# RocMan.net
KiCad netlist of a schematic drawn in EAGLE
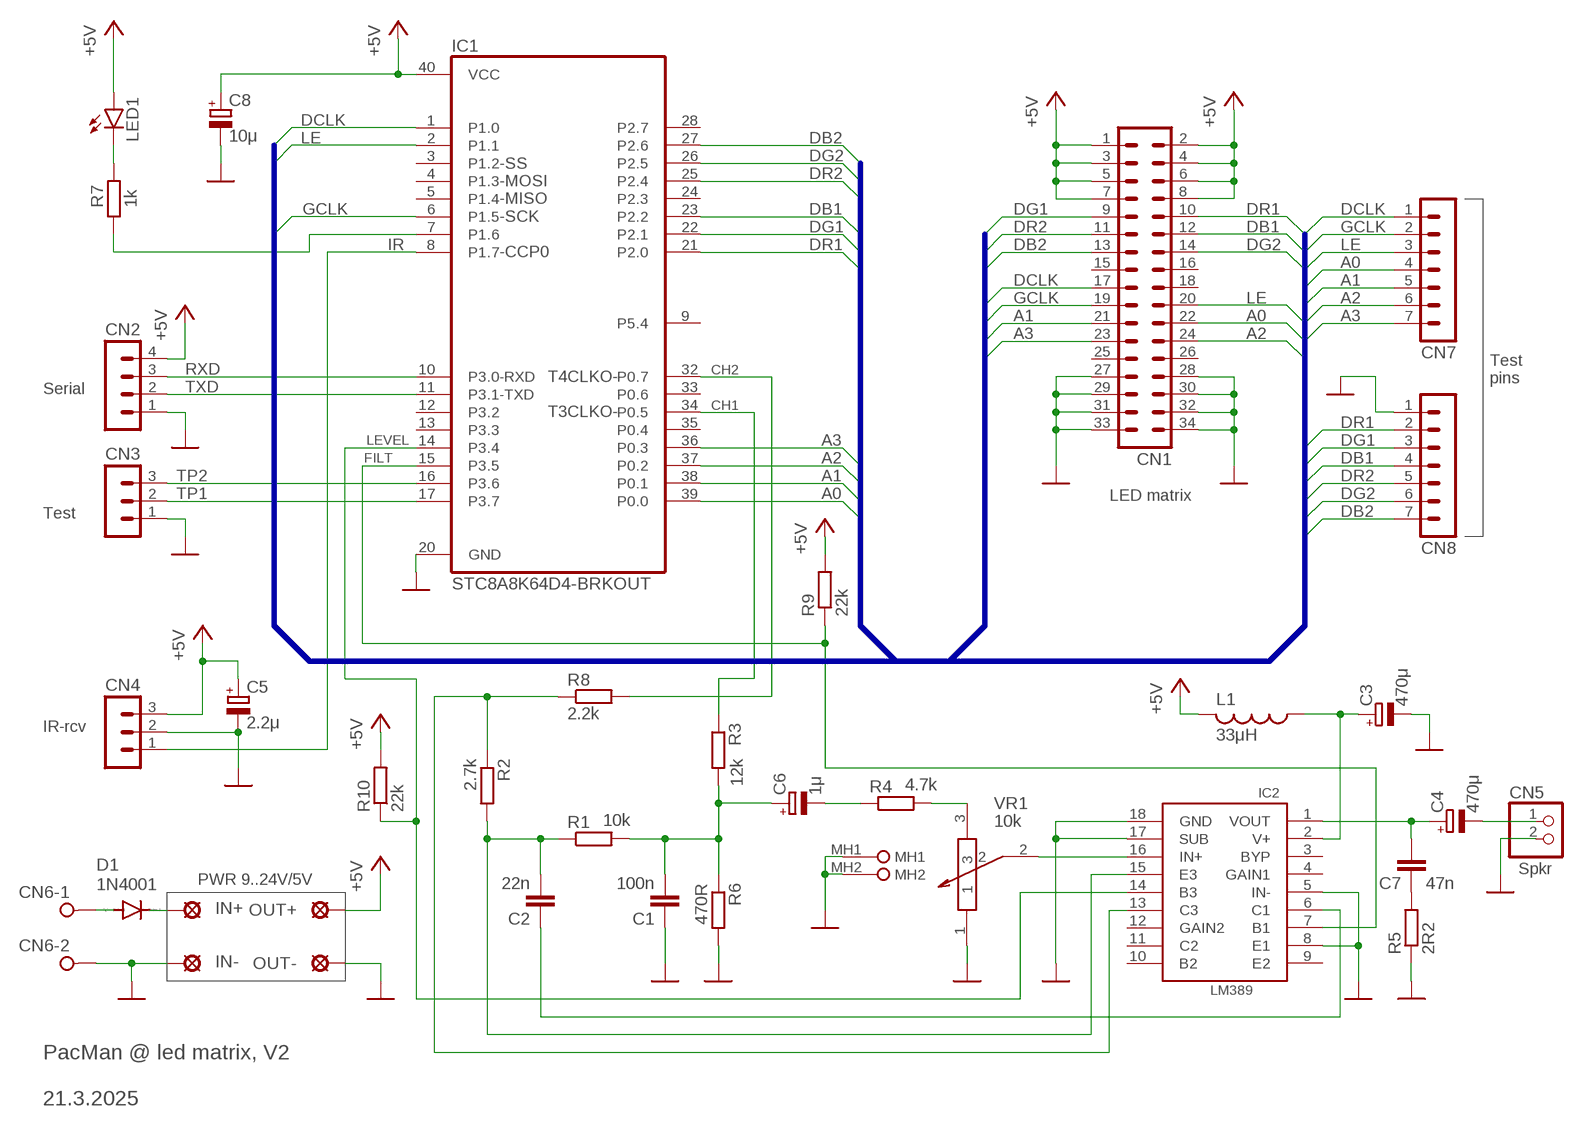
[diagram p0: schematic, sheet 1]

(export (version "E")
  (design (tool "Eeschema 10.0.6"))
  (components
    (comp (ref "C1")
      (value "100n")
      (footprint "eagle-import:C0805")
      (libsource (lib "eagle-import") (part "C-EUC0805"))
    )
    (comp (ref "C2")
      (value "22n")
      (footprint "eagle-import:C0805")
      (libsource (lib "eagle-import") (part "C-EUC0805"))
    )
    (comp (ref "C3")
      (value "470μ")
      (footprint "eagle-import:E5-10,5")
      (libsource (lib "eagle-import") (part "CPOL-EUE5-10.5"))
    )
    (comp (ref "C4")
      (value "470μ")
      (footprint "eagle-import:E5-10,5")
      (libsource (lib "eagle-import") (part "CPOL-EUE5-10.5"))
    )
    (comp (ref "C5")
      (value "2.2μ")
      (footprint "eagle-import:SMC_A")
      (libsource (lib "eagle-import") (part "CPOL-EUSMCA"))
    )
    (comp (ref "C6")
      (value "1μ")
      (footprint "eagle-import:SMC_A")
      (libsource (lib "eagle-import") (part "CPOL-EUSMCA"))
    )
    (comp (ref "C7")
      (value "47n")
      (footprint "eagle-import:C0805")
      (libsource (lib "eagle-import") (part "C-EUC0805"))
    )
    (comp (ref "C8")
      (value "10μ")
      (footprint "eagle-import:SMC_A")
      (libsource (lib "eagle-import") (part "CPOL-EUSMCA"))
    )
    (comp (ref "CN1")
      (value "ML34")
      (footprint "eagle-import:ML34")
      (libsource (lib "eagle-import") (part "ML34"))
    )
    (comp (ref "CN2")
      (value "MA04-1")
      (footprint "eagle-import:MA04-1")
      (libsource (lib "eagle-import") (part "MA04-1"))
    )
    (comp (ref "CN3")
      (value "MA03-1")
      (footprint "eagle-import:MA03-1")
      (libsource (lib "eagle-import") (part "MA03-1"))
    )
    (comp (ref "CN4")
      (value "MA03-1")
      (footprint "eagle-import:MA03-1")
      (libsource (lib "eagle-import") (part "MA03-1"))
    )
    (comp (ref "CN5")
      (value "PINHD-1X2")
      (footprint "eagle-import:1X02")
      (libsource (lib "eagle-import") (part "PINHD-1X2"))
    )
    (comp (ref "CN6")
      (value "W237-02P")
      (footprint "eagle-import:W237-132")
      (libsource (lib "eagle-import") (part "W237-02P"))
    )
    (comp (ref "CN7")
      (value "MA07-1")
      (footprint "eagle-import:MA07-1")
      (libsource (lib "eagle-import") (part "MA07-1"))
    )
    (comp (ref "CN8")
      (value "MA07-1")
      (footprint "eagle-import:MA07-1")
      (libsource (lib "eagle-import") (part "MA07-1"))
    )
    (comp (ref "D1")
      (value "1N4001")
      (footprint "eagle-import:DO41-10")
      (libsource (lib "eagle-import") (part "1N4004"))
    )
    (comp (ref "IC1")
      (value "STC8A8K64D4-BRKOUT")
      (footprint "eagle-import:DIL40")
      (libsource (lib "eagle-import") (part "STC8A8K64D4-BRKOUT"))
    )
    (comp (ref "IC2")
      (value "LM389")
      (footprint "eagle-import:DIL18")
      (libsource (lib "eagle-import") (part "LM389"))
    )
    (comp (ref "IN+")
      (value "LSP11")
      (footprint "eagle-import:LSP11")
      (libsource (lib "eagle-import") (part "LSP11"))
    )
    (comp (ref "IN-")
      (value "LSP11")
      (footprint "eagle-import:LSP11")
      (libsource (lib "eagle-import") (part "LSP11"))
    )
    (comp (ref "L1")
      (value "33μH")
      (footprint "eagle-import:L4532M")
      (libsource (lib "eagle-import") (part "L-USL4532C"))
    )
    (comp (ref "LED1")
      (value "LEDCHIP-LED0805")
      (footprint "eagle-import:CHIP-LED0805")
      (libsource (lib "eagle-import") (part "LEDCHIP-LED0805"))
    )
    (comp (ref "OUT+")
      (value "LSP11")
      (footprint "eagle-import:LSP11")
      (libsource (lib "eagle-import") (part "LSP11"))
    )
    (comp (ref "OUT-")
      (value "LSP11")
      (footprint "eagle-import:LSP11")
      (libsource (lib "eagle-import") (part "LSP11"))
    )
    (comp (ref "R1")
      (value "10k")
      (footprint "eagle-import:R0805")
      (libsource (lib "eagle-import") (part "R-EU_R0805"))
    )
    (comp (ref "R2")
      (value "2.7k")
      (footprint "eagle-import:R0805")
      (libsource (lib "eagle-import") (part "R-EU_R0805"))
    )
    (comp (ref "R3")
      (value "12k")
      (footprint "eagle-import:R0805")
      (libsource (lib "eagle-import") (part "R-EU_R0805"))
    )
    (comp (ref "R4")
      (value "4.7k")
      (footprint "eagle-import:R0805")
      (libsource (lib "eagle-import") (part "R-EU_R0805"))
    )
    (comp (ref "R5")
      (value "2R2")
      (footprint "eagle-import:R0805")
      (libsource (lib "eagle-import") (part "R-EU_R0805"))
    )
    (comp (ref "R6")
      (value "470R")
      (footprint "eagle-import:R0805")
      (libsource (lib "eagle-import") (part "R-EU_R0805"))
    )
    (comp (ref "R7")
      (value "1k")
      (footprint "eagle-import:R0805")
      (libsource (lib "eagle-import") (part "R-EU_R0805"))
    )
    (comp (ref "R8")
      (value "2.2k")
      (footprint "eagle-import:R0805")
      (libsource (lib "eagle-import") (part "R-EU_R0805"))
    )
    (comp (ref "R9")
      (value "22k")
      (footprint "eagle-import:R0805")
      (libsource (lib "eagle-import") (part "R-EU_R0805"))
    )
    (comp (ref "R10")
      (value "22k")
      (footprint "eagle-import:R0805")
      (libsource (lib "eagle-import") (part "R-EU_R0805"))
    )
    (comp (ref "VR1")
      (value "10k")
      (footprint "eagle-import:PTV09A4015FA103")
      (fields
        (field (name "MANUFACTURER_PART_NUMBER") "PTV09A-4015F-A103")
        (field (name "MOUSER_PART_NUMBER") "652-PTV09A-4015FA103")
      )
      (libsource (lib "eagle-import") (part "PTV09A-4015F-A103"))
    )
  )
  (nets
    (net (code "1") (name "+5V") (class "Default")
      (node (ref "C5") (pin "+") (pinfunction "+_+") (pintype "passive"))
      (node (ref "C8") (pin "+") (pinfunction "+_+") (pintype "passive"))
      (node (ref "CN1") (pin "1") (pinfunction "1_1") (pintype "passive"))
      (node (ref "CN1") (pin "2") (pinfunction "2_2") (pintype "passive"))
      (node (ref "CN1") (pin "3") (pinfunction "3_3") (pintype "passive"))
      (node (ref "CN1") (pin "4") (pinfunction "4_4") (pintype "passive"))
      (node (ref "CN1") (pin "5") (pinfunction "5_5") (pintype "passive"))
      (node (ref "CN1") (pin "6") (pinfunction "6_6") (pintype "passive"))
      (node (ref "CN1") (pin "7") (pinfunction "7_7") (pintype "passive"))
      (node (ref "CN1") (pin "8") (pinfunction "8_8") (pintype "passive"))
      (node (ref "CN2") (pin "4") (pinfunction "4_4") (pintype "passive"))
      (node (ref "CN4") (pin "3") (pinfunction "3_3") (pintype "passive"))
      (node (ref "IC1") (pin "40") (pinfunction "VCC_40") (pintype "power_in"))
      (node (ref "L1") (pin "2") (pinfunction "2_2") (pintype "passive"))
      (node (ref "LED1") (pin "A") (pinfunction "A_A") (pintype "passive"))
      (node (ref "OUT+") (pin "MP") (pinfunction "MP_MP") (pintype "passive"))
      (node (ref "R10") (pin "2") (pinfunction "2_2") (pintype "passive"))
      (node (ref "R9") (pin "2") (pinfunction "2_2") (pintype "passive"))
    )
    (net (code "2") (name "/A0") (class "Default")
      (node (ref "CN1") (pin "22") (pinfunction "22_22") (pintype "passive"))
      (node (ref "CN7") (pin "4") (pinfunction "4_4") (pintype "passive"))
      (node (ref "IC1") (pin "39") (pinfunction "P0.0_39") (pintype "bidirectional"))
    )
    (net (code "3") (name "/A1") (class "Default")
      (node (ref "CN1") (pin "21") (pinfunction "21_21") (pintype "passive"))
      (node (ref "CN7") (pin "5") (pinfunction "5_5") (pintype "passive"))
      (node (ref "IC1") (pin "38") (pinfunction "P0.1_38") (pintype "bidirectional"))
    )
    (net (code "4") (name "/A2") (class "Default")
      (node (ref "CN1") (pin "24") (pinfunction "24_24") (pintype "passive"))
      (node (ref "CN7") (pin "6") (pinfunction "6_6") (pintype "passive"))
      (node (ref "IC1") (pin "37") (pinfunction "P0.2_37") (pintype "bidirectional"))
    )
    (net (code "5") (name "/A3") (class "Default")
      (node (ref "CN1") (pin "23") (pinfunction "23_23") (pintype "passive"))
      (node (ref "CN7") (pin "7") (pinfunction "7_7") (pintype "passive"))
      (node (ref "IC1") (pin "36") (pinfunction "P0.3_36") (pintype "bidirectional"))
    )
    (net (code "6") (name "/CH1") (class "Default")
      (node (ref "IC1") (pin "34") (pinfunction "P0.5_34") (pintype "bidirectional"))
      (node (ref "R3") (pin "1") (pinfunction "1_1") (pintype "passive"))
    )
    (net (code "7") (name "/CH2") (class "Default")
      (node (ref "IC1") (pin "32") (pinfunction "P0.7_32") (pintype "bidirectional"))
      (node (ref "R8") (pin "2") (pinfunction "2_2") (pintype "passive"))
    )
    (net (code "8") (name "/DB1") (class "Default")
      (node (ref "CN1") (pin "12") (pinfunction "12_12") (pintype "passive"))
      (node (ref "CN8") (pin "4") (pinfunction "4_4") (pintype "passive"))
      (node (ref "IC1") (pin "23") (pinfunction "P2.2_23") (pintype "bidirectional"))
    )
    (net (code "9") (name "/DB2") (class "Default")
      (node (ref "CN1") (pin "13") (pinfunction "13_13") (pintype "passive"))
      (node (ref "CN8") (pin "7") (pinfunction "7_7") (pintype "passive"))
      (node (ref "IC1") (pin "27") (pinfunction "P2.6_27") (pintype "bidirectional"))
    )
    (net (code "10") (name "/DCLK") (class "Default")
      (node (ref "CN1") (pin "17") (pinfunction "17_17") (pintype "passive"))
      (node (ref "CN7") (pin "1") (pinfunction "1_1") (pintype "passive"))
      (node (ref "IC1") (pin "1") (pinfunction "P1.0_1") (pintype "bidirectional"))
    )
    (net (code "11") (name "/DG1") (class "Default")
      (node (ref "CN1") (pin "9") (pinfunction "9_9") (pintype "passive"))
      (node (ref "CN8") (pin "3") (pinfunction "3_3") (pintype "passive"))
      (node (ref "IC1") (pin "22") (pinfunction "P2.1_22") (pintype "bidirectional"))
    )
    (net (code "12") (name "/DG2") (class "Default")
      (node (ref "CN1") (pin "14") (pinfunction "14_14") (pintype "passive"))
      (node (ref "CN8") (pin "6") (pinfunction "6_6") (pintype "passive"))
      (node (ref "IC1") (pin "26") (pinfunction "P2.5_26") (pintype "bidirectional"))
    )
    (net (code "13") (name "/DR1") (class "Default")
      (node (ref "CN1") (pin "10") (pinfunction "10_10") (pintype "passive"))
      (node (ref "CN8") (pin "2") (pinfunction "2_2") (pintype "passive"))
      (node (ref "IC1") (pin "21") (pinfunction "P2.0_21") (pintype "bidirectional"))
    )
    (net (code "14") (name "/DR2") (class "Default")
      (node (ref "CN1") (pin "11") (pinfunction "11_11") (pintype "passive"))
      (node (ref "CN8") (pin "5") (pinfunction "5_5") (pintype "passive"))
      (node (ref "IC1") (pin "25") (pinfunction "P2.4_25") (pintype "bidirectional"))
    )
    (net (code "15") (name "/FILT") (class "Default")
      (node (ref "IC1") (pin "15") (pinfunction "P3.5_15") (pintype "bidirectional"))
      (node (ref "IC2") (pin "7") (pinfunction "B1_7") (pintype "bidirectional"))
      (node (ref "R9") (pin "1") (pinfunction "1_1") (pintype "passive"))
    )
    (net (code "16") (name "/GCLK") (class "Default")
      (node (ref "CN1") (pin "19") (pinfunction "19_19") (pintype "passive"))
      (node (ref "CN7") (pin "2") (pinfunction "2_2") (pintype "passive"))
      (node (ref "IC1") (pin "6") (pinfunction "P1.5_6") (pintype "bidirectional"))
    )
    (net (code "17") (name "/IR") (class "Default")
      (node (ref "CN4") (pin "1") (pinfunction "1_1") (pintype "passive"))
      (node (ref "IC1") (pin "8") (pinfunction "P1.7_8") (pintype "bidirectional"))
    )
    (net (code "18") (name "/LE") (class "Default")
      (node (ref "CN1") (pin "20") (pinfunction "20_20") (pintype "passive"))
      (node (ref "CN7") (pin "3") (pinfunction "3_3") (pintype "passive"))
      (node (ref "IC1") (pin "2") (pinfunction "P1.1_2") (pintype "bidirectional"))
    )
    (net (code "19") (name "/LEVEL") (class "Default")
      (node (ref "IC1") (pin "14") (pinfunction "P3.4_14") (pintype "bidirectional"))
      (node (ref "IC2") (pin "14") (pinfunction "B3_14") (pintype "bidirectional"))
      (node (ref "R10") (pin "1") (pinfunction "1_1") (pintype "passive"))
    )
    (net (code "20") (name "/RXD") (class "Default")
      (node (ref "CN2") (pin "3") (pinfunction "3_3") (pintype "passive"))
      (node (ref "IC1") (pin "10") (pinfunction "P3.0-RXD_10") (pintype "bidirectional"))
    )
    (net (code "21") (name "/TP1") (class "Default")
      (node (ref "CN3") (pin "2") (pinfunction "2_2") (pintype "passive"))
      (node (ref "IC1") (pin "17") (pinfunction "P3.7_17") (pintype "bidirectional"))
    )
    (net (code "22") (name "/TP2") (class "Default")
      (node (ref "CN3") (pin "3") (pinfunction "3_3") (pintype "passive"))
      (node (ref "IC1") (pin "16") (pinfunction "P3.6_16") (pintype "bidirectional"))
    )
    (net (code "23") (name "/TXD") (class "Default")
      (node (ref "CN2") (pin "2") (pinfunction "2_2") (pintype "passive"))
      (node (ref "IC1") (pin "11") (pinfunction "P3.1-TXD_11") (pintype "bidirectional"))
    )
    (net (code "24") (name "GND") (class "Default")
      (node (ref "C1") (pin "1") (pinfunction "1_1") (pintype "passive"))
      (node (ref "C3") (pin "-") (pinfunction "-_-") (pintype "passive"))
      (node (ref "C5") (pin "-") (pinfunction "-_-") (pintype "passive"))
      (node (ref "C8") (pin "-") (pinfunction "-_-") (pintype "passive"))
      (node (ref "CN1") (pin "27") (pinfunction "27_27") (pintype "passive"))
      (node (ref "CN1") (pin "28") (pinfunction "28_28") (pintype "passive"))
      (node (ref "CN1") (pin "29") (pinfunction "29_29") (pintype "passive"))
      (node (ref "CN1") (pin "30") (pinfunction "30_30") (pintype "passive"))
      (node (ref "CN1") (pin "31") (pinfunction "31_31") (pintype "passive"))
      (node (ref "CN1") (pin "32") (pinfunction "32_32") (pintype "passive"))
      (node (ref "CN1") (pin "33") (pinfunction "33_33") (pintype "passive"))
      (node (ref "CN1") (pin "34") (pinfunction "34_34") (pintype "passive"))
      (node (ref "CN2") (pin "1") (pinfunction "1_1") (pintype "passive"))
      (node (ref "CN3") (pin "1") (pinfunction "1_1") (pintype "passive"))
      (node (ref "CN4") (pin "2") (pinfunction "2_2") (pintype "passive"))
      (node (ref "CN5") (pin "2") (pinfunction "2_2") (pintype "passive"))
      (node (ref "CN6") (pin "2") (pinfunction "KL_2") (pintype "passive"))
      (node (ref "CN8") (pin "1") (pinfunction "1_1") (pintype "passive"))
      (node (ref "IC1") (pin "20") (pinfunction "GND_20") (pintype "power_in"))
      (node (ref "IC2") (pin "17") (pinfunction "SUB_17") (pintype "power_in"))
      (node (ref "IC2") (pin "18") (pinfunction "GND_18") (pintype "power_in"))
      (node (ref "IC2") (pin "5") (pinfunction "IN-_5") (pintype "bidirectional"))
      (node (ref "IC2") (pin "8") (pinfunction "E1_8") (pintype "bidirectional"))
      (node (ref "IN-") (pin "MP") (pinfunction "MP_MP") (pintype "passive"))
      (node (ref "OUT-") (pin "MP") (pinfunction "MP_MP") (pintype "passive"))
      (node (ref "R5") (pin "1") (pinfunction "1_1") (pintype "passive"))
      (node (ref "R6") (pin "2") (pinfunction "2_2") (pintype "passive"))
      (node (ref "VR1") (pin "1") (pinfunction "1_1") (pintype "bidirectional"))
      (node (ref "VR1") (pin "MH1") (pinfunction "MH1_MH1") (pintype "bidirectional"))
      (node (ref "VR1") (pin "MH2") (pinfunction "MH2_MH2") (pintype "bidirectional"))
    )
    (net (code "25") (name "Net-(C1-Pad2)") (class "Default")
      (node (ref "C1") (pin "2") (pinfunction "2_2") (pintype "passive"))
      (node (ref "C6") (pin "+") (pinfunction "+_+") (pintype "passive"))
      (node (ref "R1") (pin "2") (pinfunction "2_2") (pintype "passive"))
      (node (ref "R3") (pin "2") (pinfunction "2_2") (pintype "passive"))
      (node (ref "R6") (pin "1") (pinfunction "1_1") (pintype "passive"))
    )
    (net (code "26") (name "Net-(C4-Pad-)") (class "Default")
      (node (ref "C4") (pin "-") (pinfunction "-_-") (pintype "passive"))
      (node (ref "CN5") (pin "1") (pinfunction "1_1") (pintype "passive"))
    )
    (net (code "27") (name "Net-(C6-Pad-)") (class "Default")
      (node (ref "C6") (pin "-") (pinfunction "-_-") (pintype "passive"))
      (node (ref "R4") (pin "1") (pinfunction "1_1") (pintype "passive"))
    )
    (net (code "28") (name "Net-(C7-Pad1)") (class "Default")
      (node (ref "C7") (pin "1") (pinfunction "1_1") (pintype "passive"))
      (node (ref "R5") (pin "2") (pinfunction "2_2") (pintype "passive"))
    )
    (net (code "29") (name "Net-(CN6A-KL)") (class "Default")
      (node (ref "CN6") (pin "1") (pinfunction "KL_1") (pintype "passive"))
      (node (ref "D1") (pin "A") (pinfunction "A_A") (pintype "passive"))
    )
    (net (code "30") (name "Net-(D1-PadC)") (class "Default")
      (node (ref "D1") (pin "C") (pinfunction "C_C") (pintype "passive"))
      (node (ref "IN+") (pin "MP") (pinfunction "MP_MP") (pintype "passive"))
    )
    (net (code "31") (name "Net-(IC1-P1.6)") (class "Default")
      (node (ref "IC1") (pin "7") (pinfunction "P1.6_7") (pintype "bidirectional"))
      (node (ref "R7") (pin "1") (pinfunction "1_1") (pintype "passive"))
    )
    (net (code "32") (name "Net-(IC2-C1)") (class "Default")
      (node (ref "C2") (pin "1") (pinfunction "1_1") (pintype "passive"))
      (node (ref "IC2") (pin "6") (pinfunction "C1_6") (pintype "bidirectional"))
    )
    (net (code "33") (name "Net-(IC2-C3)") (class "Default")
      (node (ref "IC2") (pin "13") (pinfunction "C3_13") (pintype "bidirectional"))
      (node (ref "R2") (pin "1") (pinfunction "1_1") (pintype "passive"))
      (node (ref "R8") (pin "1") (pinfunction "1_1") (pintype "passive"))
    )
    (net (code "34") (name "Net-(IC2-E3)") (class "Default")
      (node (ref "C2") (pin "2") (pinfunction "2_2") (pintype "passive"))
      (node (ref "IC2") (pin "15") (pinfunction "E3_15") (pintype "bidirectional"))
      (node (ref "R1") (pin "1") (pinfunction "1_1") (pintype "passive"))
      (node (ref "R2") (pin "2") (pinfunction "2_2") (pintype "passive"))
    )
    (net (code "35") (name "Net-(IC2-IN+)") (class "Default")
      (node (ref "IC2") (pin "16") (pinfunction "IN+_16") (pintype "bidirectional"))
      (node (ref "VR1") (pin "2") (pinfunction "2_2") (pintype "bidirectional"))
    )
    (net (code "36") (name "Net-(IC2-V+)") (class "Default")
      (node (ref "C3") (pin "+") (pinfunction "+_+") (pintype "passive"))
      (node (ref "IC2") (pin "2") (pinfunction "V+_2") (pintype "power_in"))
      (node (ref "L1") (pin "1") (pinfunction "1_1") (pintype "passive"))
    )
    (net (code "37") (name "Net-(IC2-VOUT)") (class "Default")
      (node (ref "C4") (pin "+") (pinfunction "+_+") (pintype "passive"))
      (node (ref "C7") (pin "2") (pinfunction "2_2") (pintype "passive"))
      (node (ref "IC2") (pin "1") (pinfunction "VOUT_1") (pintype "bidirectional"))
    )
    (net (code "38") (name "Net-(LED1-PadC)") (class "Default")
      (node (ref "LED1") (pin "C") (pinfunction "C_C") (pintype "passive"))
      (node (ref "R7") (pin "2") (pinfunction "2_2") (pintype "passive"))
    )
    (net (code "39") (name "Net-(R4-Pad2)") (class "Default")
      (node (ref "R4") (pin "2") (pinfunction "2_2") (pintype "passive"))
      (node (ref "VR1") (pin "3") (pinfunction "3_3") (pintype "bidirectional"))
    )
    (net (code "40") (name "unconnected-(CN1-Pad15)") (class "Default")
      (node (ref "CN1") (pin "15") (pinfunction "15_15") (pintype "passive"))
    )
    (net (code "41") (name "unconnected-(CN1-Pad16)") (class "Default")
      (node (ref "CN1") (pin "16") (pinfunction "16_16") (pintype "passive"))
    )
    (net (code "42") (name "unconnected-(CN1-Pad18)") (class "Default")
      (node (ref "CN1") (pin "18") (pinfunction "18_18") (pintype "passive"))
    )
    (net (code "43") (name "unconnected-(CN1-Pad25)") (class "Default")
      (node (ref "CN1") (pin "25") (pinfunction "25_25") (pintype "passive"))
    )
    (net (code "44") (name "unconnected-(CN1-Pad26)") (class "Default")
      (node (ref "CN1") (pin "26") (pinfunction "26_26") (pintype "passive"))
    )
    (net (code "45") (name "unconnected-(IC1-P0.4-Pad35)") (class "Default")
      (node (ref "IC1") (pin "35") (pinfunction "P0.4_35") (pintype "bidirectional"))
    )
    (net (code "46") (name "unconnected-(IC1-P0.6-Pad33)") (class "Default")
      (node (ref "IC1") (pin "33") (pinfunction "P0.6_33") (pintype "bidirectional"))
    )
    (net (code "47") (name "unconnected-(IC1-P1.2-Pad3)") (class "Default")
      (node (ref "IC1") (pin "3") (pinfunction "P1.2_3") (pintype "bidirectional"))
    )
    (net (code "48") (name "unconnected-(IC1-P1.3-Pad4)") (class "Default")
      (node (ref "IC1") (pin "4") (pinfunction "P1.3_4") (pintype "bidirectional"))
    )
    (net (code "49") (name "unconnected-(IC1-P1.4-Pad5)") (class "Default")
      (node (ref "IC1") (pin "5") (pinfunction "P1.4_5") (pintype "bidirectional"))
    )
    (net (code "50") (name "unconnected-(IC1-P2.3-Pad24)") (class "Default")
      (node (ref "IC1") (pin "24") (pinfunction "P2.3_24") (pintype "bidirectional"))
    )
    (net (code "51") (name "unconnected-(IC1-P2.7-Pad28)") (class "Default")
      (node (ref "IC1") (pin "28") (pinfunction "P2.7_28") (pintype "bidirectional"))
    )
    (net (code "52") (name "unconnected-(IC1-P3.2-Pad12)") (class "Default")
      (node (ref "IC1") (pin "12") (pinfunction "P3.2_12") (pintype "bidirectional"))
    )
    (net (code "53") (name "unconnected-(IC1-P3.3-Pad13)") (class "Default")
      (node (ref "IC1") (pin "13") (pinfunction "P3.3_13") (pintype "bidirectional"))
    )
    (net (code "54") (name "unconnected-(IC1-P5.4-Pad9)") (class "Default")
      (node (ref "IC1") (pin "9") (pinfunction "P5.4_9") (pintype "input"))
    )
    (net (code "55") (name "unconnected-(IC2-B2-Pad10)") (class "Default")
      (node (ref "IC2") (pin "10") (pinfunction "B2_10") (pintype "bidirectional"))
    )
    (net (code "56") (name "unconnected-(IC2-BYP-Pad3)") (class "Default")
      (node (ref "IC2") (pin "3") (pinfunction "BYP_3") (pintype "bidirectional"))
    )
    (net (code "57") (name "unconnected-(IC2-C2-Pad11)") (class "Default")
      (node (ref "IC2") (pin "11") (pinfunction "C2_11") (pintype "bidirectional"))
    )
    (net (code "58") (name "unconnected-(IC2-E2-Pad9)") (class "Default")
      (node (ref "IC2") (pin "9") (pinfunction "E2_9") (pintype "bidirectional"))
    )
    (net (code "59") (name "unconnected-(IC2-GAIN1-Pad4)") (class "Default")
      (node (ref "IC2") (pin "4") (pinfunction "GAIN1_4") (pintype "bidirectional"))
    )
    (net (code "60") (name "unconnected-(IC2-GAIN2-Pad12)") (class "Default")
      (node (ref "IC2") (pin "12") (pinfunction "GAIN2_12") (pintype "bidirectional"))
    )
  )
)
